# CAN.net
KiCad netlist of a schematic drawn in Altium Designer
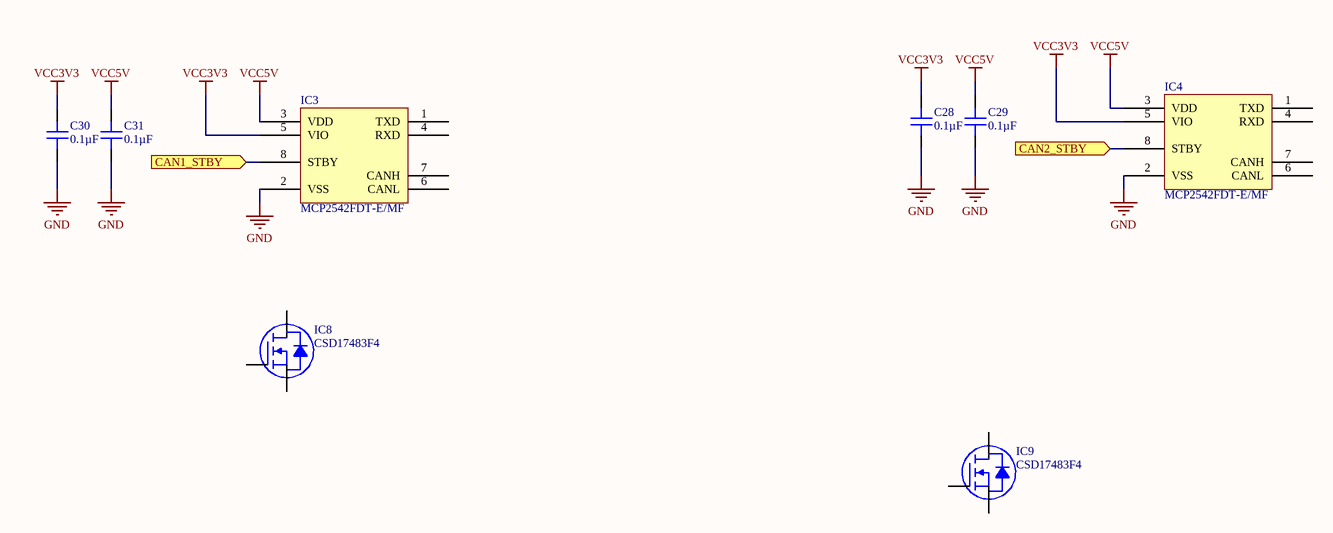
[diagram p0: CAN.SchDoc]

(export (version "E")
  (design (tool "Eeschema 10.0.6"))
  (components
    (comp (ref "C28")
      (value "0.1µF")
      (footprint "CAP 0201_0603")
      (description "CAP CER 0.1UF 16V X5R 0201")
      (fields (field (name "PART NUMBER") "EMK063BJ104KP-F") (field (name "MANUFACTURER") "Taiyo Yuden"))
      (libsource (lib "Celestial") (part "Capacitor"))
    )
    (comp (ref "C29")
      (value "0.1µF")
      (footprint "CAP 0201_0603")
      (description "CAP CER 0.1UF 16V X5R 0201")
      (fields (field (name "PART NUMBER") "EMK063BJ104KP-F") (field (name "MANUFACTURER") "Taiyo Yuden"))
      (libsource (lib "Celestial") (part "Capacitor"))
    )
    (comp (ref "C30")
      (value "0.1µF")
      (footprint "CAP 0201_0603")
      (description "CAP CER 0.1UF 16V X5R 0201")
      (fields (field (name "PART NUMBER") "EMK063BJ104KP-F") (field (name "MANUFACTURER") "Taiyo Yuden"))
      (libsource (lib "Celestial") (part "Capacitor"))
    )
    (comp (ref "C31")
      (value "0.1µF")
      (footprint "CAP 0201_0603")
      (description "CAP CER 0.1UF 16V X5R 0201")
      (fields (field (name "PART NUMBER") "EMK063BJ104KP-F") (field (name "MANUFACTURER") "Taiyo Yuden"))
      (libsource (lib "Celestial") (part "Capacitor"))
    )
    (comp (ref "IC3")
      (value "MCP2542FDT-E/MF")
      (footprint "MICROCHIP DFN-8 3X3MM")
      (description "IC TRANSCEIVER 1/1 8DFN")
      (fields (field (name "MANUFACTURER") "Microchip Technology"))
      (libsource (lib "Celestial") (part "MICROCHIP MCP2542FD"))
    )
    (comp (ref "IC4")
      (value "MCP2542FDT-E/MF")
      (footprint "MICROCHIP DFN-8 3X3MM")
      (description "IC TRANSCEIVER 1/1 8DFN")
      (fields (field (name "MANUFACTURER") "Microchip Technology"))
      (libsource (lib "Celestial") (part "MICROCHIP MCP2542FD"))
    )
    (comp (ref "IC8")
      (value "CSD17483F4")
      (footprint "TI 3-XFDFN F4 YJC")
      (description "MOSFET N-CH 30V 1.5A 3PICOSTAR")
      (fields (field (name "MANUFACTURER") "Texas Instruments"))
      (libsource (lib "Celestial") (part "TI CSD MOSFET N-CH F4"))
    )
    (comp (ref "IC9")
      (value "CSD17483F4")
      (footprint "TI 3-XFDFN F4 YJC")
      (description "MOSFET N-CH 30V 1.5A 3PICOSTAR")
      (fields (field (name "MANUFACTURER") "Texas Instruments"))
      (libsource (lib "Celestial") (part "TI CSD MOSFET N-CH F4"))
    )
  )
  (nets
    (net (code "1") (name "/CAN1_STBY") (class "Default")
      (node (ref "IC3") (pin "8") (pinfunction "STBY_8") (pintype "passive"))
    )
    (net (code "2") (name "/CAN2_STBY") (class "Default")
      (node (ref "IC4") (pin "8") (pinfunction "STBY_8") (pintype "passive"))
    )
    (net (code "3") (name "GND") (class "Default")
      (node (ref "C28") (pin "1") (pinfunction "1_1") (pintype "passive"))
      (node (ref "C29") (pin "1") (pinfunction "1_1") (pintype "passive"))
      (node (ref "C30") (pin "1") (pinfunction "1_1") (pintype "passive"))
      (node (ref "C31") (pin "1") (pinfunction "1_1") (pintype "passive"))
      (node (ref "IC3") (pin "2") (pinfunction "VSS_2") (pintype "passive"))
      (node (ref "IC4") (pin "2") (pinfunction "VSS_2") (pintype "passive"))
    )
    (net (code "4") (name "VCC3V3") (class "Default")
      (node (ref "C28") (pin "2") (pinfunction "2_2") (pintype "passive"))
      (node (ref "C30") (pin "2") (pinfunction "2_2") (pintype "passive"))
      (node (ref "IC3") (pin "5") (pinfunction "VIO_5") (pintype "passive"))
      (node (ref "IC4") (pin "5") (pinfunction "VIO_5") (pintype "passive"))
    )
    (net (code "5") (name "VCC5V") (class "Default")
      (node (ref "C29") (pin "2") (pinfunction "2_2") (pintype "passive"))
      (node (ref "C31") (pin "2") (pinfunction "2_2") (pintype "passive"))
      (node (ref "IC3") (pin "3") (pinfunction "VDD_3") (pintype "passive"))
      (node (ref "IC4") (pin "3") (pinfunction "VDD_3") (pintype "passive"))
    )
    (net (code "6") (name "unconnected-(IC3-CANH-Pad7)") (class "Default")
      (node (ref "IC3") (pin "7") (pinfunction "CANH_7") (pintype "passive"))
    )
    (net (code "7") (name "unconnected-(IC3-CANL-Pad6)") (class "Default")
      (node (ref "IC3") (pin "6") (pinfunction "CANL_6") (pintype "passive"))
    )
    (net (code "8") (name "unconnected-(IC3-RXD-Pad4)") (class "Default")
      (node (ref "IC3") (pin "4") (pinfunction "RXD_4") (pintype "passive"))
    )
    (net (code "9") (name "unconnected-(IC3-TXD-Pad1)") (class "Default")
      (node (ref "IC3") (pin "1") (pinfunction "TXD_1") (pintype "passive"))
    )
    (net (code "10") (name "unconnected-(IC4-CANH-Pad7)") (class "Default")
      (node (ref "IC4") (pin "7") (pinfunction "CANH_7") (pintype "passive"))
    )
    (net (code "11") (name "unconnected-(IC4-CANL-Pad6)") (class "Default")
      (node (ref "IC4") (pin "6") (pinfunction "CANL_6") (pintype "passive"))
    )
    (net (code "12") (name "unconnected-(IC4-RXD-Pad4)") (class "Default")
      (node (ref "IC4") (pin "4") (pinfunction "RXD_4") (pintype "passive"))
    )
    (net (code "13") (name "unconnected-(IC4-TXD-Pad1)") (class "Default")
      (node (ref "IC4") (pin "1") (pinfunction "TXD_1") (pintype "passive"))
    )
    (net (code "14") (name "unconnected-(IC8-PadD)") (class "Default")
      (node (ref "IC8") (pin "D") (pinfunction "D_D") (pintype "passive"))
    )
    (net (code "15") (name "unconnected-(IC8-PadG)") (class "Default")
      (node (ref "IC8") (pin "G") (pinfunction "G_G") (pintype "passive"))
    )
    (net (code "16") (name "unconnected-(IC8-PadS)") (class "Default")
      (node (ref "IC8") (pin "S") (pinfunction "S_S") (pintype "passive"))
    )
    (net (code "17") (name "unconnected-(IC9-PadD)") (class "Default")
      (node (ref "IC9") (pin "D") (pinfunction "D_D") (pintype "passive"))
    )
    (net (code "18") (name "unconnected-(IC9-PadG)") (class "Default")
      (node (ref "IC9") (pin "G") (pinfunction "G_G") (pintype "passive"))
    )
    (net (code "19") (name "unconnected-(IC9-PadS)") (class "Default")
      (node (ref "IC9") (pin "S") (pinfunction "S_S") (pintype "passive"))
    )
  )
)
